# Balanced_LC_Filter.net
KiCad netlist of a schematic drawn in Altium Designer
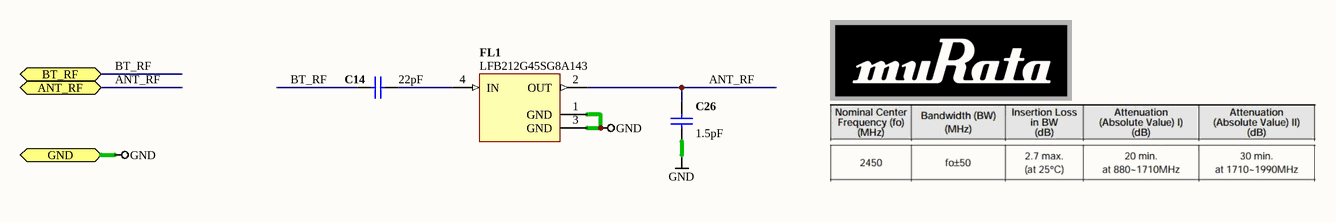
[diagram p0: Balanced_LC_Filter.SchDoc]

(export (version "E")
  (design (tool "Eeschema 10.0.6"))
  (components
    (comp (ref "C14")
      (value "22pF")
      (footprint "CAPC0402(1005)60_N")
      (description "CAP 22pF 16V ±0.25pF 0402 (1005 Metric) Thickness 0.6mm SMD")
      (fields (field (name "TOLERANCE") "±0.25pF") (field (name "Comment") "CAP 22pF 16V 0402(1005)"))
      (libsource (lib "Altium Content Vault") (part "CMP-1034-00899-1"))
    )
    (comp (ref "C26")
      (value "1.5pF")
      (footprint "CAPC0402(1005)60_N")
      (description "CAP 1.5pF 10V ±0.1pF 0402 (1005 Metric) Thickness 0.6mm SMD")
      (fields (field (name "TOLERANCE") "±0.1pF") (field (name "Comment") "CAP 1.5pF 10V 0402(1005)"))
      (libsource (lib "Altium Content Vault") (part "CMP-1034-00102-1"))
    )
    (comp (ref "FL1")
      (value "LFB212G45SG8A143")
      (footprint "MUR-LFB212G45SG8A143-4")
      (description "LFB21(0805)_SG Series Filter for Wireless LAN/Bluetooth, 2400-2500 MHz, 2 x 1.25 x 0.95 mm")
      (fields (field (name "MANUFACTURER") "Murata"))
      (libsource (lib "Altium Content Vault") (part "MURA-LFB212G45SG8A143-4"))
    )
  )
  (nets
    (net (code "1") (name "/ANT_RF") (class "Default")
      (node (ref "C26") (pin "2") (pinfunction "2_2") (pintype "passive"))
      (node (ref "FL1") (pin "2") (pinfunction "OUT_2") (pintype "output"))
    )
    (net (code "2") (name "/BT_RF") (class "Default")
      (node (ref "C14") (pin "1") (pinfunction "1_1") (pintype "passive"))
    )
    (net (code "3") (name "GND") (class "Default")
      (node (ref "C26") (pin "1") (pinfunction "1_1") (pintype "passive"))
      (node (ref "FL1") (pin "1") (pinfunction "GND_1") (pintype "power_in"))
      (node (ref "FL1") (pin "3") (pinfunction "GND_3") (pintype "power_in"))
    )
    (net (code "4") (name "Net-(FL1-IN)") (class "Default")
      (node (ref "C14") (pin "2") (pinfunction "2_2") (pintype "passive"))
      (node (ref "FL1") (pin "4") (pinfunction "IN_4") (pintype "input"))
    )
  )
)
